# Sensor_Board.net
KiCad netlist of a schematic drawn in Altium Designer
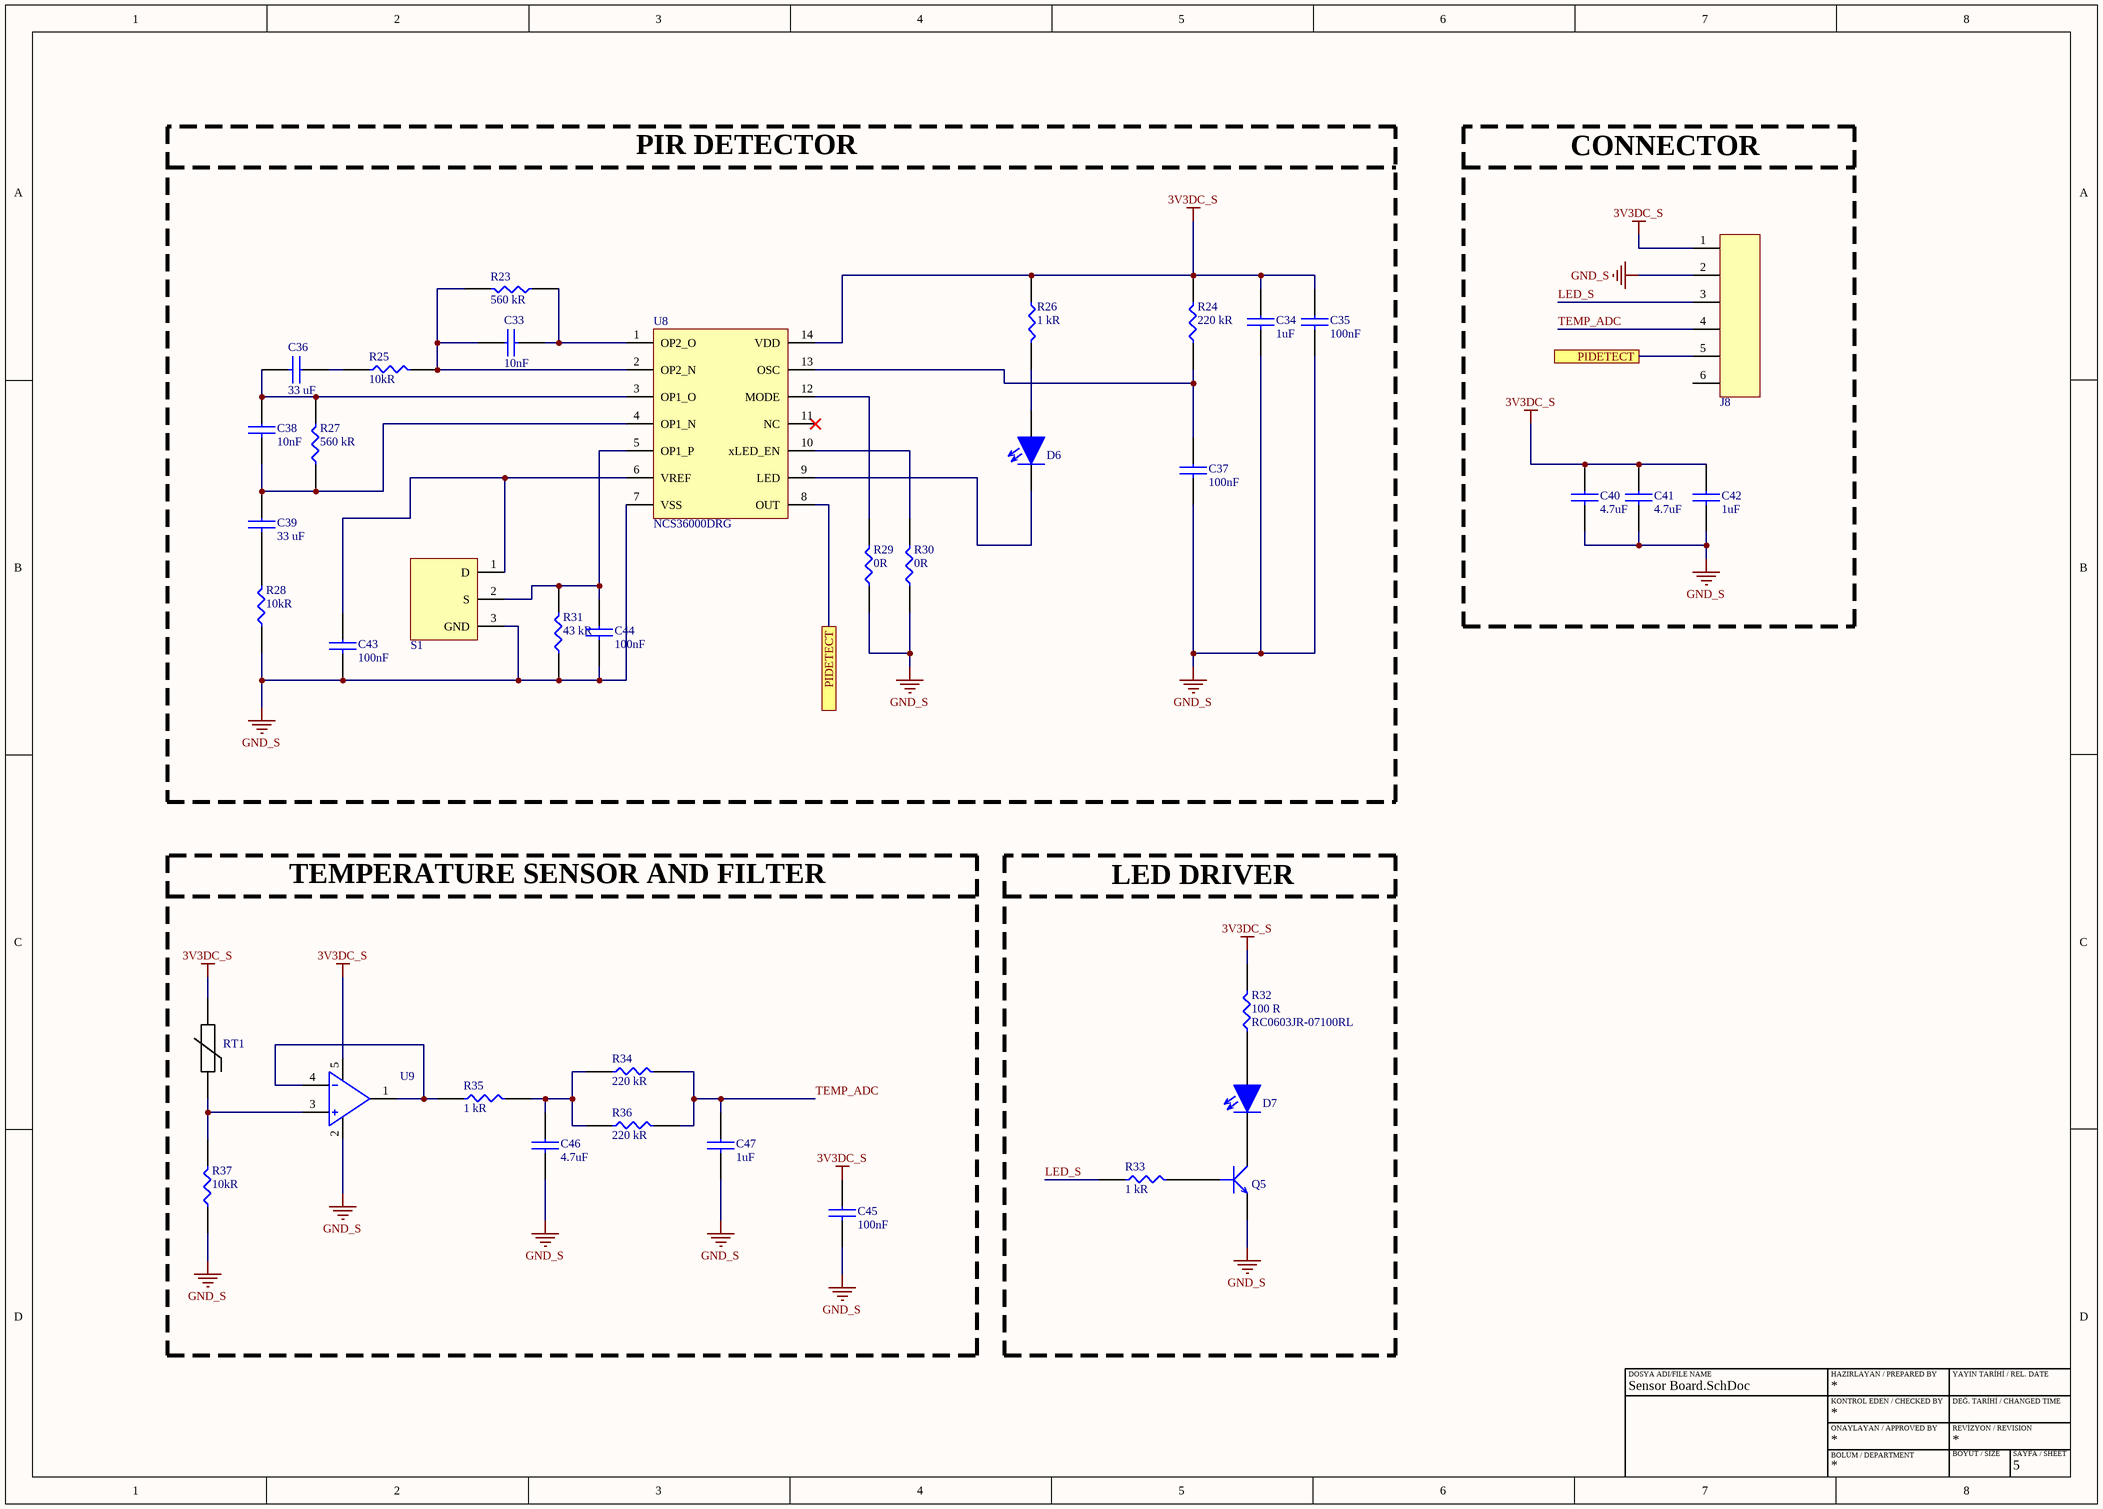
[diagram p0: Sensor Board.SchDoc]

(export (version "E")
  (design (tool "Eeschema 10.0.6"))
  (components
    (comp (ref "C33")
      (value "10nF")
      (footprint "CAP_0603")
      (description "CAP CER 10nF 10% 0603")
      (fields
        (field (name "MANUFACTURER") "Walsin Technologies")
        (field (name "MANUFACTURER PART NUMBER") "0603B103K160CT")
        (field (name "DESIGNED BY") "MCP")
      )
      (libsource (lib "Integrated_Library1") (part "CAP CER 10nF 0603"))
    )
    (comp (ref "C34")
      (value "1uF")
      (footprint "CAP_0805")
      (description "CAP CER 1uF 10% 0805")
      (fields
        (field (name "MANUFACTURER") "Samsung")
        (field (name "MANUFACTURER PART NUMBER") "CL21B105KBFNNNE")
        (field (name "DESIGNED BY") "MCP")
      )
      (libsource (lib "Integrated_Library1") (part "CAP CER 1uF 0805"))
    )
    (comp (ref "C35")
      (value "100nF")
      (footprint "CAP_0805")
      (description "CAP CER 100nF 10% 0805")
      (fields
        (field (name "MANUFACTURER") "Samsung")
        (field (name "MANUFACTURER PART NUMBER") "CL21B104KBCNNNC")
        (field (name "DESIGNED BY") "MCP")
      )
      (libsource (lib "Integrated_Library1") (part "CAP CER 100nF 0805"))
    )
    (comp (ref "C36")
      (value "33 uF")
      (footprint "CAP_1206")
      (description "CAP CER 33uF %20 1206")
      (fields
        (field (name "MANUFACTURER") "TDK")
        (field (name "MANUFACTURER PART NUMBER") "C3216X5R1E336M160AC")
      )
      (libsource (lib "Integrated_Library1") (part "CAP CER 33uF 1206"))
    )
    (comp (ref "C37")
      (value "100nF")
      (footprint "CAP_0603")
      (description "CAP CER 100nF 10% 0603")
      (fields
        (field (name "MANUFACTURER") "KEMET")
        (field (name "MANUFACTURER PART NUMBER") "C0603C104K5RACTU")
        (field (name "DESIGNED BY") "MCP")
      )
      (libsource (lib "Integrated_Library1") (part "CAP CER 100nF 0603"))
    )
    (comp (ref "C38")
      (value "10nF")
      (footprint "CAP_0603")
      (description "CAP CER 10nF 10% 0603")
      (fields
        (field (name "MANUFACTURER") "Walsin Technologies")
        (field (name "MANUFACTURER PART NUMBER") "0603B103K160CT")
        (field (name "DESIGNED BY") "MCP")
      )
      (libsource (lib "Integrated_Library1") (part "CAP CER 10nF 0603"))
    )
    (comp (ref "C39")
      (value "33 uF")
      (footprint "CAP_1206")
      (description "CAP CER 33uF %20 1206")
      (fields
        (field (name "MANUFACTURER") "TDK")
        (field (name "MANUFACTURER PART NUMBER") "C3216X5R1E336M160AC")
      )
      (libsource (lib "Integrated_Library1") (part "CAP CER 33uF 1206"))
    )
    (comp (ref "C40")
      (value "4.7uF")
      (footprint "CAP_0805")
      (description "CAP CER 4.7uF 10% 0805")
      (fields
        (field (name "MANUFACTURER") "Samsung")
        (field (name "MANUFACTURER PART NUMBER") "CL21A475KAQNNNE")
        (field (name "DESIGNED BY") "MCP")
      )
      (libsource (lib "Integrated_Library1") (part "CAP CER 4.7uF 0805"))
    )
    (comp (ref "C41")
      (value "4.7uF")
      (footprint "CAP_0805")
      (description "CAP CER 4.7uF 10% 0805")
      (fields
        (field (name "MANUFACTURER") "Samsung")
        (field (name "MANUFACTURER PART NUMBER") "CL21A475KAQNNNE")
        (field (name "DESIGNED BY") "MCP")
      )
      (libsource (lib "Integrated_Library1") (part "CAP CER 4.7uF 0805"))
    )
    (comp (ref "C42")
      (value "1uF")
      (footprint "CAP_0805")
      (description "CAP CER 1uF 10% 0805")
      (fields
        (field (name "MANUFACTURER") "Samsung")
        (field (name "MANUFACTURER PART NUMBER") "CL21B105KBFNNNE")
        (field (name "DESIGNED BY") "MCP")
      )
      (libsource (lib "Integrated_Library1") (part "CAP CER 1uF 0805"))
    )
    (comp (ref "C43")
      (value "100nF")
      (footprint "CAP_0603")
      (description "CAP CER 100nF 10% 0603")
      (fields
        (field (name "MANUFACTURER") "KEMET")
        (field (name "MANUFACTURER PART NUMBER") "C0603C104K5RACTU")
        (field (name "DESIGNED BY") "MCP")
      )
      (libsource (lib "Integrated_Library1") (part "CAP CER 100nF 0603"))
    )
    (comp (ref "C44")
      (value "100nF")
      (footprint "CAP_0603")
      (description "CAP CER 100nF 10% 0603")
      (fields
        (field (name "MANUFACTURER") "KEMET")
        (field (name "MANUFACTURER PART NUMBER") "C0603C104K5RACTU")
        (field (name "DESIGNED BY") "MCP")
      )
      (libsource (lib "Integrated_Library1") (part "CAP CER 100nF 0603"))
    )
    (comp (ref "C45")
      (value "100nF")
      (footprint "CAP_0603")
      (description "CAP CER 100nF 10% 0603")
      (fields
        (field (name "MANUFACTURER") "KEMET")
        (field (name "MANUFACTURER PART NUMBER") "C0603C104K5RACTU")
        (field (name "DESIGNED BY") "MCP")
      )
      (libsource (lib "Integrated_Library1") (part "CAP CER 100nF 0603"))
    )
    (comp (ref "C46")
      (value "4.7uF")
      (footprint "CAP_0805")
      (description "CAP CER 4.7uF 10% 0805")
      (fields
        (field (name "MANUFACTURER") "Samsung")
        (field (name "MANUFACTURER PART NUMBER") "CL21A475KAQNNNE")
        (field (name "DESIGNED BY") "MCP")
      )
      (libsource (lib "Integrated_Library1") (part "CAP CER 4.7uF 0805"))
    )
    (comp (ref "C47")
      (value "1uF")
      (footprint "CAP_0805")
      (description "CAP CER 1uF 10% 0805")
      (fields
        (field (name "MANUFACTURER") "Samsung")
        (field (name "MANUFACTURER PART NUMBER") "CL21B105KBFNNNE")
        (field (name "DESIGNED BY") "MCP")
      )
      (libsource (lib "Integrated_Library1") (part "CAP CER 1uF 0805"))
    )
    (comp (ref "D6")
      (value "LTST-C171GKT")
      (footprint "LED_GREEN_0805")
      (description "Single Color LED, Green, Water Clear, 1.4mm")
      (fields (field (name "MANUFACTURER") "Vishay Lite-On"))
      (libsource (lib "Integrated_Library1") (part "LED GREEN 0805"))
    )
    (comp (ref "D7")
      (value "LH R974-LP-1")
      (footprint "LED_RED_0805")
      (libsource (lib "Integrated_Library1") (part "LED RED 0805"))
    )
    (comp (ref "J8")
      (value "64800611622_CONN_6PIN")
      (footprint "64800611622_CONN_6PIN")
      (description "1.50 mm 6 pin connector")
      (fields
        (field (name "MANUFACTURER") "Wurth Electronics")
        (field (name "MANUFACTURER PART NUMBER") "64800611622")
      )
      (libsource (lib "Integrated_Library1") (part "64800611622_CONN_6PIN"))
    )
    (comp (ref "Q5")
      (value "MMBT3904.7.F")
      (footprint "SOT-23F")
      (description "Small Signal Bipolar Transistor, 0.2A I(C), 40V V(BR)CEO, 1-Element, NPN, Silicon")
      (fields
        (field (name "MANUFACTURER") "Diodes Zetex")
        (field (name "MANUFACTURER PART NUMBER") "MMBT3904-7-F")
        (field (name "DESIGNED BY") "MCP")
      )
      (libsource (lib "Integrated_Library1") (part "MMBT3904.7.F"))
    )
    (comp (ref "R23")
      (value "560 kR")
      (footprint "RES_0603")
      (fields
        (field (name "MANUFACTURER") "Yageo")
        (field (name "MANUFACTURER PART NUMBER") "RC0603JR-07560KL")
        (field (name "TOLERANCE") "5%")
      )
      (libsource (lib "Integrated_Library1") (part "RES 560K OHM 0603"))
    )
    (comp (ref "R24")
      (value "220 kR")
      (footprint "RES_0603")
      (fields
        (field (name "MANUFACTURER") "Yageo")
        (field (name "MANUFACTURER PART NUMBER") "RC0603JR-07220KL")
        (field (name "TOLERANCE") "5%")
      )
      (libsource (lib "Integrated_Library1") (part "RES 220K OHM 0603"))
    )
    (comp (ref "R25")
      (value "10kR")
      (footprint "RES_0603")
      (fields
        (field (name "MANUFACTURER") "Yageo")
        (field (name "MANUFACTURER PART NUMBER") "RC0603FR-0710KL")
        (field (name "TOLERANCE") "1%")
        (field (name "DESIGNED BY") "MCP")
      )
      (libsource (lib "Integrated_Library1") (part "RES 10K OHM 0603"))
    )
    (comp (ref "R26")
      (value "1 kR")
      (footprint "RES_0603")
      (fields
        (field (name "MANUFACTURER") "Stackpole Electronics")
        (field (name "MANUFACTURER PART NUMBER") "RMCF0603FT1K00")
        (field (name "TOLERANCE") "1%")
      )
      (libsource (lib "Integrated_Library1") (part "RES 1K OHM 0603"))
    )
    (comp (ref "R27")
      (value "560 kR")
      (footprint "RES_0603")
      (fields
        (field (name "MANUFACTURER") "Yageo")
        (field (name "MANUFACTURER PART NUMBER") "RC0603JR-07560KL")
        (field (name "TOLERANCE") "5%")
      )
      (libsource (lib "Integrated_Library1") (part "RES 560K OHM 0603"))
    )
    (comp (ref "R28")
      (value "10kR")
      (footprint "RES_0603")
      (fields
        (field (name "MANUFACTURER") "Yageo")
        (field (name "MANUFACTURER PART NUMBER") "RC0603FR-0710KL")
        (field (name "TOLERANCE") "1%")
        (field (name "DESIGNED BY") "MCP")
      )
      (libsource (lib "Integrated_Library1") (part "RES 10K OHM 0603"))
    )
    (comp (ref "R29")
      (value "0R")
      (footprint "RES_0603")
      (description "Metal Glaze/thick Film, 0.1W, 0ohm, Surface Mount, 0603")
      (fields
        (field (name "MANUFACTURER") "Yageo")
        (field (name "MANUFACTURER PART NUMBER") "RC0603JR-070RL")
        (field (name "DESIGNED BY") "MCP")
      )
      (libsource (lib "Integrated_Library1") (part "RES 0 OHM 0603"))
    )
    (comp (ref "R30")
      (value "0R")
      (footprint "RES_0603")
      (description "Metal Glaze/thick Film, 0.1W, 0ohm, Surface Mount, 0603")
      (fields
        (field (name "MANUFACTURER") "Yageo")
        (field (name "MANUFACTURER PART NUMBER") "RC0603JR-070RL")
        (field (name "DESIGNED BY") "MCP")
      )
      (libsource (lib "Integrated_Library1") (part "RES 0 OHM 0603"))
    )
    (comp (ref "R31")
      (value "43 kR")
      (footprint "RES_0603")
      (fields
        (field (name "MANUFACTURER") "Yageo")
        (field (name "MANUFACTURER PART NUMBER") "RC0603JR-0743KL")
        (field (name "TOLERANCE") "5%")
      )
      (libsource (lib "Integrated_Library1") (part "RES 43K OHM 0603"))
    )
    (comp (ref "R32")
      (value "RC0603JR-07100RL")
      (footprint "RES_0603")
      (fields
        (field (name "MANUFACTURER") "Yageo")
        (field (name "TOLERANCE") "5%")
        (field (name "POWER") "100mW")
        (field (name "ALTIUM_VALUE") "100 R")
      )
      (libsource (lib "Integrated_Library1") (part "RES 100 OHM 0603"))
    )
    (comp (ref "R33")
      (value "1 kR")
      (footprint "RES_0603")
      (fields
        (field (name "MANUFACTURER") "Stackpole Electronics")
        (field (name "MANUFACTURER PART NUMBER") "RMCF0603FT1K00")
        (field (name "TOLERANCE") "1%")
      )
      (libsource (lib "Integrated_Library1") (part "RES 1K OHM 0603"))
    )
    (comp (ref "R34")
      (value "220 kR")
      (footprint "RES_0603")
      (fields
        (field (name "MANUFACTURER") "Yageo")
        (field (name "MANUFACTURER PART NUMBER") "RC0603JR-07220KL")
        (field (name "TOLERANCE") "5%")
      )
      (libsource (lib "Integrated_Library1") (part "RES 220K OHM 0603"))
    )
    (comp (ref "R35")
      (value "1 kR")
      (footprint "RES_0603")
      (fields
        (field (name "MANUFACTURER") "Stackpole Electronics")
        (field (name "MANUFACTURER PART NUMBER") "RMCF0603FT1K00")
        (field (name "TOLERANCE") "1%")
      )
      (libsource (lib "Integrated_Library1") (part "RES 1K OHM 0603"))
    )
    (comp (ref "R36")
      (value "220 kR")
      (footprint "RES_0603")
      (fields
        (field (name "MANUFACTURER") "Yageo")
        (field (name "MANUFACTURER PART NUMBER") "RC0603JR-07220KL")
        (field (name "TOLERANCE") "5%")
      )
      (libsource (lib "Integrated_Library1") (part "RES 220K OHM 0603"))
    )
    (comp (ref "R37")
      (value "10kR")
      (footprint "RES_0603")
      (fields
        (field (name "MANUFACTURER") "Yageo")
        (field (name "MANUFACTURER PART NUMBER") "RC0603FR-0710KL")
        (field (name "TOLERANCE") "1%")
        (field (name "DESIGNED BY") "MCP")
      )
      (libsource (lib "Integrated_Library1") (part "RES 10K OHM 0603"))
    )
    (comp (ref "RT1")
      (value "TFPT1206L1002FM")
      (footprint "RES_1206")
      (description "PTC Thermistor, 10K Ohm, Surface Mount")
      (fields
        (field (name "MANUFACTURER") "Vishay Dale")
        (field (name "TOLERANCE") "1%")
        (field (name "DESIGNED BY") "MCP")
      )
      (libsource (lib "Integrated_Library1") (part "TFPT1206L1002FM"))
    )
    (comp (ref "S1")
      (value "LHI 878/3902")
      (footprint "LHI 878/3902")
      (description "Sensor PIR (Passive Infrared) TO-205AA, TO-5-3 Metal Can")
      (fields (field (name "MANUFACTURER") "Excelitas Technology") (field (name "DESIGNED BY") "MCP"))
      (libsource (lib "Integrated_Library1") (part "LHI 878/3902"))
    )
    (comp (ref "U8")
      (value "NCS36000DRG")
      (footprint "SOIC-14")
      (description "Analog Circuit, 1 Func, CMOS, PDSO14")
      (fields (field (name "MANUFACTURER") "onsemi"))
      (libsource (lib "Integrated_Library1") (part "NCS36000"))
    )
    (comp (ref "U9")
      (value "OPA314AIDBVR")
      (footprint "SOT23-5")
      (description "Operational Amplifier, 1 Func, 2500uV Offset-Max, CMOS, PDSO5")
      (fields (field (name "MANUFACTURER") "Texas Instruments") (field (name "POWER") "No"))
      (libsource (lib "Integrated_Library1") (part "OPA314"))
    )
  )
  (nets
    (net (code "1") (name "/LED_S") (class "Default")
      (node (ref "J8") (pin "3") (pintype "passive"))
      (node (ref "R33") (pin "1") (pinfunction "1_1") (pintype "passive"))
    )
    (net (code "2") (name "/PIDETECT") (class "Default")
      (node (ref "J8") (pin "5") (pintype "passive"))
      (node (ref "U8") (pin "8") (pinfunction "OUT_8") (pintype "passive"))
    )
    (net (code "3") (name "/TEMP_ADC") (class "Default")
      (node (ref "C47") (pin "2") (pinfunction "2_2") (pintype "passive"))
      (node (ref "J8") (pin "4") (pintype "passive"))
      (node (ref "R34") (pin "2") (pinfunction "2_2") (pintype "passive"))
      (node (ref "R36") (pin "2") (pinfunction "2_2") (pintype "passive"))
    )
    (net (code "4") (name "3V3DC_S") (class "Default")
      (node (ref "C34") (pin "2") (pinfunction "2_2") (pintype "passive"))
      (node (ref "C35") (pin "2") (pinfunction "2_2") (pintype "passive"))
      (node (ref "C40") (pin "2") (pinfunction "2_2") (pintype "passive"))
      (node (ref "C41") (pin "2") (pinfunction "2_2") (pintype "passive"))
      (node (ref "C42") (pin "2") (pinfunction "2_2") (pintype "passive"))
      (node (ref "C45") (pin "2") (pinfunction "2_2") (pintype "passive"))
      (node (ref "J8") (pin "1") (pintype "passive"))
      (node (ref "R24") (pin "2") (pinfunction "2_2") (pintype "passive"))
      (node (ref "R26") (pin "1") (pinfunction "1_1") (pintype "passive"))
      (node (ref "R32") (pin "2") (pinfunction "2_2") (pintype "passive"))
      (node (ref "RT1") (pin "2") (pinfunction "2_2") (pintype "passive"))
      (node (ref "U8") (pin "14") (pinfunction "VDD_14") (pintype "passive"))
      (node (ref "U9") (pin "5") (pinfunction "5_5") (pintype "passive"))
    )
    (net (code "5") (name "GND_S") (class "Default")
      (node (ref "C34") (pin "1") (pinfunction "1_1") (pintype "passive"))
      (node (ref "C35") (pin "1") (pinfunction "1_1") (pintype "passive"))
      (node (ref "C37") (pin "1") (pinfunction "1_1") (pintype "passive"))
      (node (ref "C40") (pin "1") (pinfunction "1_1") (pintype "passive"))
      (node (ref "C41") (pin "1") (pinfunction "1_1") (pintype "passive"))
      (node (ref "C42") (pin "1") (pinfunction "1_1") (pintype "passive"))
      (node (ref "C43") (pin "1") (pinfunction "1_1") (pintype "passive"))
      (node (ref "C44") (pin "1") (pinfunction "1_1") (pintype "passive"))
      (node (ref "C45") (pin "1") (pinfunction "1_1") (pintype "passive"))
      (node (ref "C46") (pin "1") (pinfunction "1_1") (pintype "passive"))
      (node (ref "C47") (pin "1") (pinfunction "1_1") (pintype "passive"))
      (node (ref "J8") (pin "2") (pintype "passive"))
      (node (ref "Q5") (pin "2") (pinfunction "E_2") (pintype "passive"))
      (node (ref "R28") (pin "1") (pinfunction "1_1") (pintype "passive"))
      (node (ref "R29") (pin "1") (pinfunction "1_1") (pintype "passive"))
      (node (ref "R30") (pin "1") (pinfunction "1_1") (pintype "passive"))
      (node (ref "R31") (pin "1") (pinfunction "1_1") (pintype "passive"))
      (node (ref "R37") (pin "1") (pinfunction "1_1") (pintype "passive"))
      (node (ref "S1") (pin "3") (pinfunction "GND_3") (pintype "passive"))
      (node (ref "U8") (pin "7") (pinfunction "VSS_7") (pintype "passive"))
      (node (ref "U9") (pin "2") (pinfunction "2_2") (pintype "passive"))
    )
    (net (code "6") (name "Net-(C36-Pad2)") (class "Default")
      (node (ref "C36") (pin "2") (pinfunction "2_2") (pintype "passive"))
      (node (ref "R25") (pin "1") (pinfunction "1_1") (pintype "passive"))
    )
    (net (code "7") (name "Net-(C39-Pad1)") (class "Default")
      (node (ref "C39") (pin "1") (pinfunction "1_1") (pintype "passive"))
      (node (ref "R28") (pin "2") (pinfunction "2_2") (pintype "passive"))
    )
    (net (code "8") (name "Net-(C46-Pad2)") (class "Default")
      (node (ref "C46") (pin "2") (pinfunction "2_2") (pintype "passive"))
      (node (ref "R34") (pin "1") (pinfunction "1_1") (pintype "passive"))
      (node (ref "R35") (pin "2") (pinfunction "2_2") (pintype "passive"))
      (node (ref "R36") (pin "1") (pinfunction "1_1") (pintype "passive"))
    )
    (net (code "9") (name "Net-(D6-Pad2)") (class "Default")
      (node (ref "D6") (pin "2") (pinfunction "2_2") (pintype "passive"))
      (node (ref "R26") (pin "2") (pinfunction "2_2") (pintype "passive"))
    )
    (net (code "10") (name "Net-(D7-Pad2)") (class "Default")
      (node (ref "D7") (pin "2") (pinfunction "2_2") (pintype "passive"))
      (node (ref "R32") (pin "1") (pinfunction "1_1") (pintype "passive"))
    )
    (net (code "11") (name "Net-(Q5-B)") (class "Default")
      (node (ref "Q5") (pin "1") (pinfunction "B_1") (pintype "passive"))
      (node (ref "R33") (pin "2") (pinfunction "2_2") (pintype "passive"))
    )
    (net (code "12") (name "Net-(Q5-C)") (class "Default")
      (node (ref "D7") (pin "1") (pinfunction "1_1") (pintype "passive"))
      (node (ref "Q5") (pin "3") (pinfunction "C_3") (pintype "passive"))
    )
    (net (code "13") (name "Net-(R35-Pad1)") (class "Default")
      (node (ref "R35") (pin "1") (pinfunction "1_1") (pintype "passive"))
      (node (ref "U9") (pin "1") (pinfunction "1_1") (pintype "passive"))
      (node (ref "U9") (pin "4") (pinfunction "4_4") (pintype "passive"))
    )
    (net (code "14") (name "Net-(R37-Pad2)") (class "Default")
      (node (ref "R37") (pin "2") (pinfunction "2_2") (pintype "passive"))
      (node (ref "RT1") (pin "1") (pinfunction "1_1") (pintype "passive"))
      (node (ref "U9") (pin "3") (pinfunction "3_3") (pintype "passive"))
    )
    (net (code "15") (name "Net-(S1-D)") (class "Default")
      (node (ref "C43") (pin "2") (pinfunction "2_2") (pintype "passive"))
      (node (ref "S1") (pin "1") (pinfunction "D_1") (pintype "passive"))
      (node (ref "U8") (pin "6") (pinfunction "VREF_6") (pintype "passive"))
    )
    (net (code "16") (name "Net-(S1-S)") (class "Default")
      (node (ref "C44") (pin "2") (pinfunction "2_2") (pintype "passive"))
      (node (ref "R31") (pin "2") (pinfunction "2_2") (pintype "passive"))
      (node (ref "S1") (pin "2") (pinfunction "S_2") (pintype "passive"))
      (node (ref "U8") (pin "5") (pinfunction "OP1_P_5") (pintype "passive"))
    )
    (net (code "17") (name "Net-(U8-LED)") (class "Default")
      (node (ref "D6") (pin "1") (pinfunction "1_1") (pintype "passive"))
      (node (ref "U8") (pin "9") (pinfunction "LED_9") (pintype "passive"))
    )
    (net (code "18") (name "Net-(U8-MODE)") (class "Default")
      (node (ref "R29") (pin "2") (pinfunction "2_2") (pintype "passive"))
      (node (ref "U8") (pin "12") (pinfunction "MODE_12") (pintype "passive"))
    )
    (net (code "19") (name "Net-(U8-OP1_N)") (class "Default")
      (node (ref "C38") (pin "1") (pinfunction "1_1") (pintype "passive"))
      (node (ref "C39") (pin "2") (pinfunction "2_2") (pintype "passive"))
      (node (ref "R27") (pin "1") (pinfunction "1_1") (pintype "passive"))
      (node (ref "U8") (pin "4") (pinfunction "OP1_N_4") (pintype "passive"))
    )
    (net (code "20") (name "Net-(U8-OP1_O)") (class "Default")
      (node (ref "C36") (pin "1") (pinfunction "1_1") (pintype "passive"))
      (node (ref "C38") (pin "2") (pinfunction "2_2") (pintype "passive"))
      (node (ref "R27") (pin "2") (pinfunction "2_2") (pintype "passive"))
      (node (ref "U8") (pin "3") (pinfunction "OP1_O_3") (pintype "passive"))
    )
    (net (code "21") (name "Net-(U8-OP2_N)") (class "Default")
      (node (ref "C33") (pin "2") (pinfunction "2_2") (pintype "passive"))
      (node (ref "R23") (pin "2") (pinfunction "2_2") (pintype "passive"))
      (node (ref "R25") (pin "2") (pinfunction "2_2") (pintype "passive"))
      (node (ref "U8") (pin "2") (pinfunction "OP2_N_2") (pintype "passive"))
    )
    (net (code "22") (name "Net-(U8-OP2_O)") (class "Default")
      (node (ref "C33") (pin "1") (pinfunction "1_1") (pintype "passive"))
      (node (ref "R23") (pin "1") (pinfunction "1_1") (pintype "passive"))
      (node (ref "U8") (pin "1") (pinfunction "OP2_O_1") (pintype "passive"))
    )
    (net (code "23") (name "Net-(U8-OSC)") (class "Default")
      (node (ref "C37") (pin "2") (pinfunction "2_2") (pintype "passive"))
      (node (ref "R24") (pin "1") (pinfunction "1_1") (pintype "passive"))
      (node (ref "U8") (pin "13") (pinfunction "OSC_13") (pintype "passive"))
    )
    (net (code "24") (name "Net-(U8-xLED_EN)") (class "Default")
      (node (ref "R30") (pin "2") (pinfunction "2_2") (pintype "passive"))
      (node (ref "U8") (pin "10") (pinfunction "xLED_EN_10") (pintype "passive"))
    )
    (net (code "25") (name "unconnected-(J8-Pad6)") (class "Default")
      (node (ref "J8") (pin "6") (pintype "passive"))
    )
    (net (code "26") (name "unconnected-(U8-NC-Pad11)") (class "Default")
      (node (ref "U8") (pin "11") (pinfunction "NC_11") (pintype "passive+no_connect"))
    )
  )
)
